# NST_Current.net
KiCad netlist of a schematic drawn in EAGLE
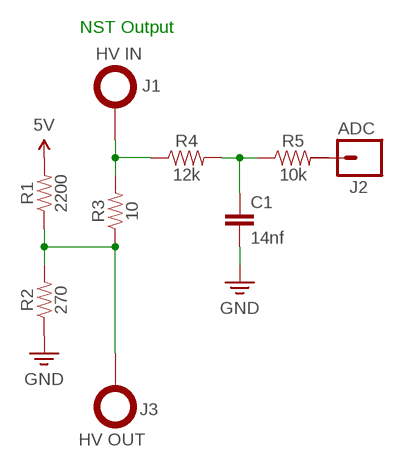
[diagram p0: schematic, sheet 1]

(export (version "E")
  (design (tool "Eeschema 10.0.6"))
  (components
    (comp (ref "C1")
      (value "14nf")
      (footprint "eagle-import:CAP-PTH-10MM")
      (libsource (lib "eagle-import") (part "10NF-PTH-10MM-10000V-1-%"))
    )
    (comp (ref "J1")
      (value "HV IN")
      (footprint "eagle-import:LUG_SQUARE_M6")
      (libsource (lib "eagle-import") (part "TERMINAL_M6"))
    )
    (comp (ref "J2")
      (value "ADC")
      (footprint "eagle-import:1X01_2MM")
      (libsource (lib "eagle-import") (part "CONN_01PTH_2MM"))
    )
    (comp (ref "J3")
      (value "HV OUT")
      (footprint "eagle-import:LUG_SQUARE_M6")
      (libsource (lib "eagle-import") (part "TERMINAL_M6"))
    )
    (comp (ref "R1")
      (value "2200")
      (footprint "eagle-import:AXIAL-0.3")
      (libsource (lib "eagle-import") (part "15KOHM-HORIZ-1/4W-5%"))
    )
    (comp (ref "R2")
      (value "270")
      (footprint "eagle-import:AXIAL-0.3")
      (libsource (lib "eagle-import") (part "15KOHM-HORIZ-1/4W-5%"))
    )
    (comp (ref "R3")
      (value "10")
      (footprint "eagle-import:AXIAL-0.3")
      (libsource (lib "eagle-import") (part "15KOHM-HORIZ-1/4W-5%"))
    )
    (comp (ref "R4")
      (value "12k")
      (footprint "eagle-import:AXIAL-0.3")
      (libsource (lib "eagle-import") (part "15KOHM-HORIZ-1/4W-5%"))
    )
    (comp (ref "R5")
      (value "10k")
      (footprint "eagle-import:AXIAL-0.3")
      (libsource (lib "eagle-import") (part "15KOHM-HORIZ-1/4W-5%"))
    )
  )
  (nets
    (net (code "1") (name "5V") (class "Default")
      (node (ref "R1") (pin "P$2") (pinfunction "2_P$2") (pintype "passive"))
    )
    (net (code "2") (name "GND") (class "Default")
      (node (ref "C1") (pin "2") (pinfunction "2_2") (pintype "passive"))
      (node (ref "R2") (pin "P$1") (pinfunction "1_P$1") (pintype "passive"))
    )
    (net (code "3") (name "Net-(R1-1)") (class "Default")
      (node (ref "J3") (pin "P$1") (pinfunction "P$1_P$1") (pintype "passive"))
      (node (ref "R1") (pin "P$1") (pinfunction "1_P$1") (pintype "passive"))
      (node (ref "R2") (pin "P$2") (pinfunction "2_P$2") (pintype "passive"))
      (node (ref "R3") (pin "P$1") (pinfunction "1_P$1") (pintype "passive"))
    )
    (net (code "4") (name "Net-(R3-2)") (class "Default")
      (node (ref "J1") (pin "P$1") (pinfunction "P$1_P$1") (pintype "passive"))
      (node (ref "R3") (pin "P$2") (pinfunction "2_P$2") (pintype "passive"))
      (node (ref "R4") (pin "P$1") (pinfunction "1_P$1") (pintype "passive"))
    )
    (net (code "5") (name "Net-(R4-2)") (class "Default")
      (node (ref "C1") (pin "1") (pinfunction "1_1") (pintype "passive"))
      (node (ref "R4") (pin "P$2") (pinfunction "2_P$2") (pintype "passive"))
      (node (ref "R5") (pin "P$1") (pinfunction "1_P$1") (pintype "passive"))
    )
    (net (code "6") (name "unconnected-(J2-Pad1)") (class "Default")
      (node (ref "J2") (pin "1") (pinfunction "1_1") (pintype "passive"))
    )
    (net (code "7") (name "unconnected-(R5-2-PadP$2)") (class "Default")
      (node (ref "R5") (pin "P$2") (pinfunction "2_P$2") (pintype "passive"))
    )
  )
)
